# Schematic.net
KiCad netlist of a schematic drawn in EasyEDA
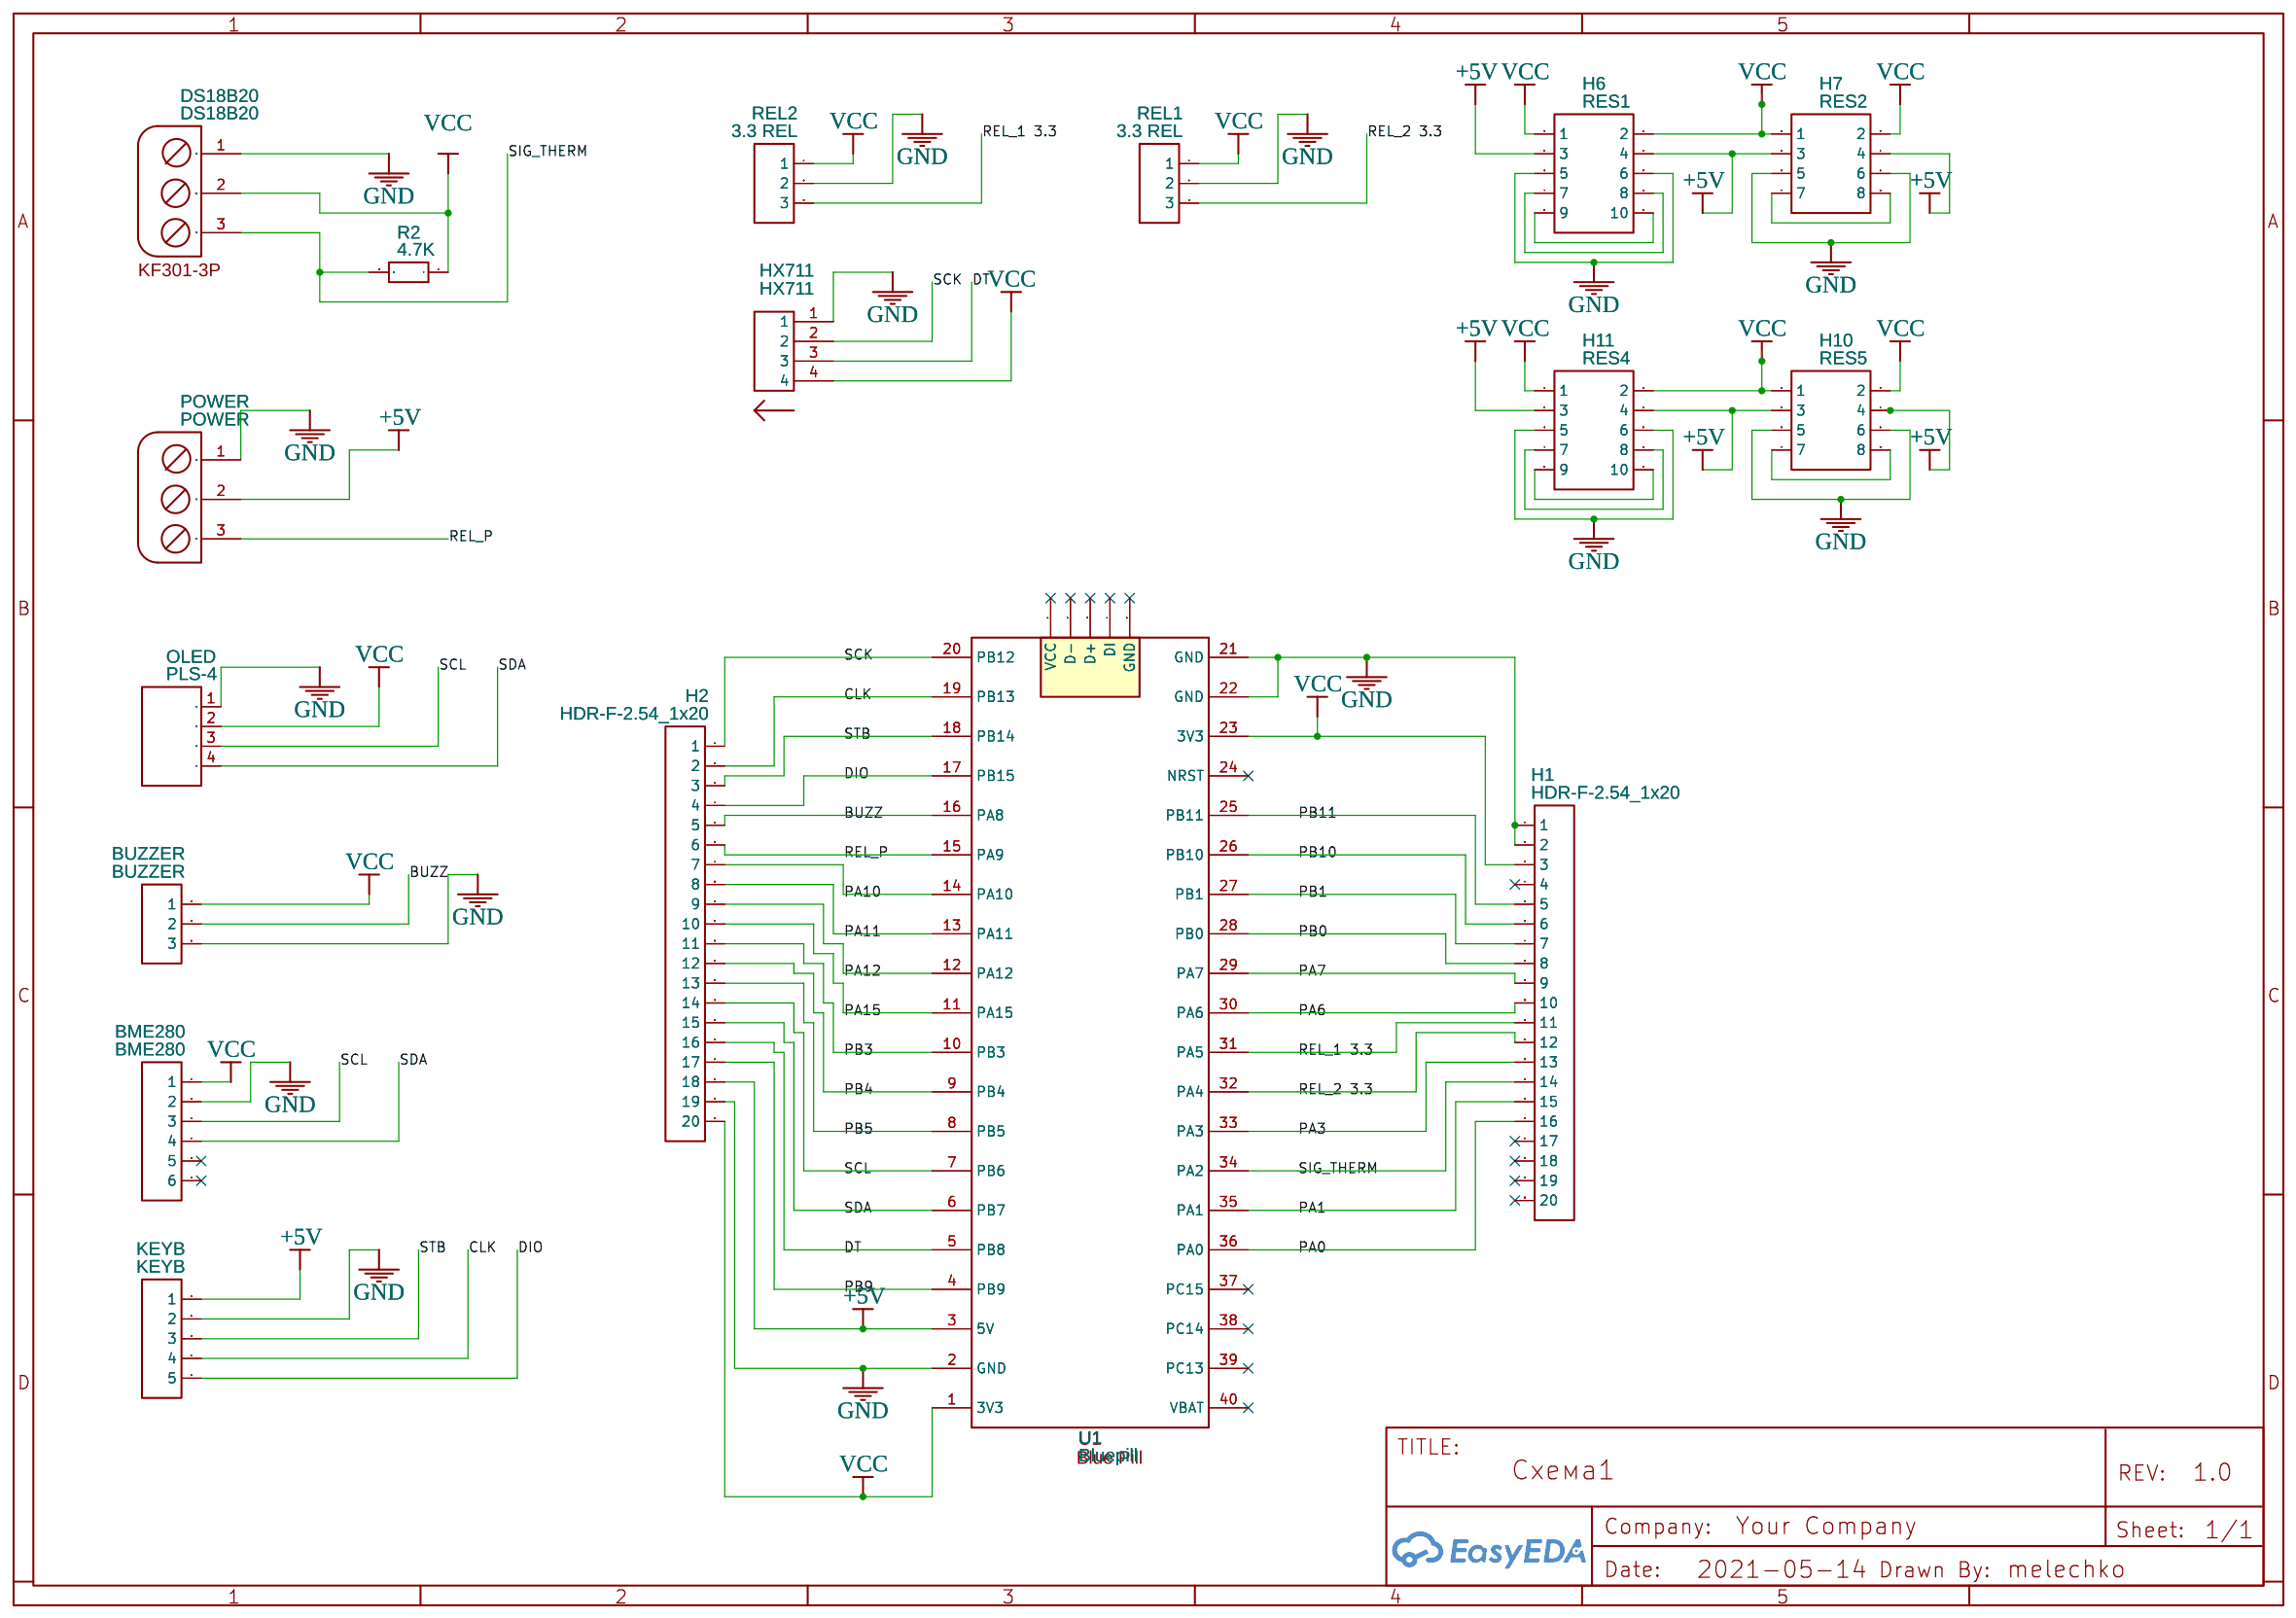
[diagram p0: schematic sheet]

(export (version "E")
  (design (tool "Eeschema 10.0.6"))
  (components
    (comp (ref "BME280")
      (value "BME280")
      (fields (field (name "BOM_Supplier Part") "C40877"))
      (libsource (lib "") (part "HDR-F-2.54_1x6"))
    )
    (comp (ref "BUZZER")
      (value "BUZZER")
      (fields (field (name "BOM_Supplier Part") "C146690"))
      (libsource (lib "") (part "HDR-F-2.54_1x3_1"))
    )
    (comp (ref "DS18B20") (value "DS18B20") (libsource (lib "") (part "KF301-3P")))
    (comp (ref "H1")
      (value "HDR-F-2.54_1x20")
      (fields (field (name "BOM_Supplier Part") "C50984"))
      (libsource (lib "") (part "HDR-F-2.54_1x20_1"))
    )
    (comp (ref "H2")
      (value "HDR-F-2.54_1x20")
      (fields (field (name "BOM_Supplier Part") "C50984"))
      (libsource (lib "") (part "HDR-F-2.54_1x20"))
    )
    (comp (ref "H6")
      (value "RES1")
      (fields (field (name "BOM_Supplier Part") "C30419"))
      (libsource (lib "") (part "HDR-F-2.54_2x5"))
    )
    (comp (ref "H7")
      (value "RES2")
      (fields (field (name "BOM_Supplier Part") "C239344"))
      (libsource (lib "") (part "HDR-F-2.54_2x4"))
    )
    (comp (ref "H10")
      (value "RES5")
      (fields (field (name "BOM_Supplier Part") "C239344"))
      (libsource (lib "") (part "HDR-F-2.54_2x4"))
    )
    (comp (ref "H11")
      (value "RES4")
      (fields (field (name "BOM_Supplier Part") "C30419"))
      (libsource (lib "") (part "HDR-F-2.54_2x5"))
    )
    (comp (ref "HX711")
      (value "HX711")
      (fields (field (name "BOM_Manufacturer Part") "PLS-4R (DS1022-1x4R)"))
      (libsource (lib "") (part "PLS-4R (DS1022-1x4R)"))
    )
    (comp (ref "KEYB")
      (value "KEYB")
      (fields (field (name "BOM_Supplier Part") "C50950"))
      (libsource (lib "") (part "HDR-F-2.54_1x5"))
    )
    (comp (ref "OLED")
      (value "PLS-4")
      (fields (field (name "BOM_Manufacturer Part") "PLS-4 2,54 1x4"))
      (libsource (lib "") (part "PLS-4"))
    )
    (comp (ref "POWER") (value "POWER") (libsource (lib "") (part "KF301-3P_1")))
    (comp (ref "R2")
      (value "4.7K")
      (fields
        (field (name "BOM_Manufacturer Part") "RN 1WS 4K7 F T/B A1")
        (field (name "BOM_Supplier Part") "C433646")
      )
      (libsource (lib "") (part "RN 1WS 4K7 F T/B A1"))
    )
    (comp (ref "REL1")
      (value "3.3 REL")
      (fields (field (name "BOM_Supplier Part") "C146690"))
      (libsource (lib "") (part "HDR-F-2.54_1x3"))
    )
    (comp (ref "REL2")
      (value "3.3 REL")
      (fields (field (name "BOM_Supplier Part") "C146690"))
      (libsource (lib "") (part "HDR-F-2.54_1x3"))
    )
    (comp (ref "U1") (value "Bluepill") (libsource (lib "") (part "Bluepill")))
  )
  (nets
    (net (code "1") (name "+5V") (class "Default")
      (node (ref "H10") (pin "3") (pinfunction "3_3") (pintype "unspecified"))
      (node (ref "H10") (pin "4") (pinfunction "4_4") (pintype "unspecified"))
      (node (ref "H11") (pin "3") (pinfunction "3_3") (pintype "unspecified"))
      (node (ref "H11") (pin "4") (pinfunction "4_4") (pintype "unspecified"))
      (node (ref "H2") (pin "18") (pinfunction "18_18") (pintype "unspecified"))
      (node (ref "H6") (pin "3") (pinfunction "3_3") (pintype "unspecified"))
      (node (ref "H6") (pin "4") (pinfunction "4_4") (pintype "unspecified"))
      (node (ref "H7") (pin "3") (pinfunction "3_3") (pintype "unspecified"))
      (node (ref "H7") (pin "4") (pinfunction "4_4") (pintype "unspecified"))
      (node (ref "KEYB") (pin "1") (pinfunction "1_1") (pintype "unspecified"))
      (node (ref "POWER") (pin "2") (pinfunction "2_2") (pintype "unspecified"))
      (node (ref "U1") (pin "3") (pinfunction "5V_3") (pintype "passive"))
    )
    (net (code "2") (name "/BUZZ") (class "Default")
      (node (ref "BUZZER") (pin "2") (pinfunction "2_2") (pintype "input"))
      (node (ref "H2") (pin "5") (pinfunction "5_5") (pintype "unspecified"))
      (node (ref "U1") (pin "16") (pinfunction "PA8_16") (pintype "bidirectional"))
    )
    (net (code "3") (name "/CLK") (class "Default")
      (node (ref "H2") (pin "2") (pinfunction "2_2") (pintype "unspecified"))
      (node (ref "KEYB") (pin "4") (pinfunction "4_4") (pintype "unspecified"))
      (node (ref "U1") (pin "19") (pinfunction "PB13_19") (pintype "bidirectional"))
    )
    (net (code "4") (name "/DIO") (class "Default")
      (node (ref "H2") (pin "4") (pinfunction "4_4") (pintype "unspecified"))
      (node (ref "KEYB") (pin "5") (pinfunction "5_5") (pintype "unspecified"))
      (node (ref "U1") (pin "17") (pinfunction "PB15_17") (pintype "bidirectional"))
    )
    (net (code "5") (name "/DT") (class "Default")
      (node (ref "H2") (pin "16") (pinfunction "16_16") (pintype "unspecified"))
      (node (ref "HX711") (pin "3") (pinfunction "3_3") (pintype "unspecified"))
      (node (ref "U1") (pin "5") (pinfunction "PB8_5") (pintype "bidirectional"))
    )
    (net (code "6") (name "/PA0") (class "Default")
      (node (ref "H1") (pin "16") (pinfunction "16_16") (pintype "unspecified"))
      (node (ref "U1") (pin "36") (pinfunction "PA0_36") (pintype "bidirectional"))
    )
    (net (code "7") (name "/PA1") (class "Default")
      (node (ref "H1") (pin "15") (pinfunction "15_15") (pintype "unspecified"))
      (node (ref "U1") (pin "35") (pinfunction "PA1_35") (pintype "bidirectional"))
    )
    (net (code "8") (name "/PA3") (class "Default")
      (node (ref "H1") (pin "13") (pinfunction "13_13") (pintype "unspecified"))
      (node (ref "U1") (pin "33") (pinfunction "PA3_33") (pintype "bidirectional"))
    )
    (net (code "9") (name "/PA6") (class "Default")
      (node (ref "H1") (pin "10") (pinfunction "10_10") (pintype "unspecified"))
      (node (ref "U1") (pin "30") (pinfunction "PA6_30") (pintype "bidirectional"))
    )
    (net (code "10") (name "/PA7") (class "Default")
      (node (ref "H1") (pin "9") (pinfunction "9_9") (pintype "unspecified"))
      (node (ref "U1") (pin "29") (pinfunction "PA7_29") (pintype "bidirectional"))
    )
    (net (code "11") (name "/PA10") (class "Default")
      (node (ref "H2") (pin "7") (pinfunction "7_7") (pintype "unspecified"))
      (node (ref "U1") (pin "14") (pinfunction "PA10_14") (pintype "bidirectional"))
    )
    (net (code "12") (name "/PA11") (class "Default")
      (node (ref "H2") (pin "8") (pinfunction "8_8") (pintype "unspecified"))
      (node (ref "U1") (pin "13") (pinfunction "PA11_13") (pintype "bidirectional"))
    )
    (net (code "13") (name "/PA12") (class "Default")
      (node (ref "H2") (pin "9") (pinfunction "9_9") (pintype "unspecified"))
      (node (ref "U1") (pin "12") (pinfunction "PA12_12") (pintype "bidirectional"))
    )
    (net (code "14") (name "/PA15") (class "Default")
      (node (ref "H2") (pin "10") (pinfunction "10_10") (pintype "unspecified"))
      (node (ref "U1") (pin "11") (pinfunction "PA15_11") (pintype "bidirectional"))
    )
    (net (code "15") (name "/PB0") (class "Default")
      (node (ref "H1") (pin "8") (pinfunction "8_8") (pintype "unspecified"))
      (node (ref "U1") (pin "28") (pinfunction "PB0_28") (pintype "bidirectional"))
    )
    (net (code "16") (name "/PB1") (class "Default")
      (node (ref "H1") (pin "7") (pinfunction "7_7") (pintype "unspecified"))
      (node (ref "U1") (pin "27") (pinfunction "PB1_27") (pintype "bidirectional"))
    )
    (net (code "17") (name "/PB3") (class "Default")
      (node (ref "H2") (pin "11") (pinfunction "11_11") (pintype "unspecified"))
      (node (ref "U1") (pin "10") (pinfunction "PB3_10") (pintype "unspecified"))
    )
    (net (code "18") (name "/PB4") (class "Default")
      (node (ref "H2") (pin "12") (pinfunction "12_12") (pintype "unspecified"))
      (node (ref "U1") (pin "9") (pinfunction "PB4_9") (pintype "bidirectional"))
    )
    (net (code "19") (name "/PB5") (class "Default")
      (node (ref "H2") (pin "13") (pinfunction "13_13") (pintype "unspecified"))
      (node (ref "U1") (pin "8") (pinfunction "PB5_8") (pintype "bidirectional"))
    )
    (net (code "20") (name "/PB9") (class "Default")
      (node (ref "H2") (pin "17") (pinfunction "17_17") (pintype "unspecified"))
      (node (ref "U1") (pin "4") (pinfunction "PB9_4") (pintype "bidirectional"))
    )
    (net (code "21") (name "/PB10") (class "Default")
      (node (ref "H1") (pin "6") (pinfunction "6_6") (pintype "unspecified"))
      (node (ref "U1") (pin "26") (pinfunction "PB10_26") (pintype "bidirectional"))
    )
    (net (code "22") (name "/PB11") (class "Default")
      (node (ref "H1") (pin "5") (pinfunction "5_5") (pintype "unspecified"))
      (node (ref "U1") (pin "25") (pinfunction "PB11_25") (pintype "bidirectional"))
    )
    (net (code "23") (name "/REL_1 3.3") (class "Default")
      (node (ref "H1") (pin "11") (pinfunction "11_11") (pintype "unspecified"))
      (node (ref "REL2") (pin "3") (pinfunction "3_3") (pintype "input"))
      (node (ref "U1") (pin "31") (pinfunction "PA5_31") (pintype "bidirectional"))
    )
    (net (code "24") (name "/REL_2 3.3") (class "Default")
      (node (ref "H1") (pin "12") (pinfunction "12_12") (pintype "unspecified"))
      (node (ref "REL1") (pin "3") (pinfunction "3_3") (pintype "input"))
      (node (ref "U1") (pin "32") (pinfunction "PA4_32") (pintype "bidirectional"))
    )
    (net (code "25") (name "/REL_P") (class "Default")
      (node (ref "H2") (pin "6") (pinfunction "6_6") (pintype "unspecified"))
      (node (ref "POWER") (pin "3") (pinfunction "3_3") (pintype "unspecified"))
      (node (ref "U1") (pin "15") (pinfunction "PA9_15") (pintype "bidirectional"))
    )
    (net (code "26") (name "/SCK") (class "Default")
      (node (ref "H2") (pin "1") (pinfunction "1_1") (pintype "unspecified"))
      (node (ref "HX711") (pin "2") (pinfunction "2_2") (pintype "unspecified"))
      (node (ref "U1") (pin "20") (pinfunction "PB12_20") (pintype "bidirectional"))
    )
    (net (code "27") (name "/SCL") (class "Default")
      (node (ref "BME280") (pin "3") (pinfunction "3_3") (pintype "input"))
      (node (ref "H2") (pin "14") (pinfunction "14_14") (pintype "unspecified"))
      (node (ref "OLED") (pin "3") (pinfunction "3_3") (pintype "unspecified"))
      (node (ref "U1") (pin "7") (pinfunction "PB6_7") (pintype "bidirectional"))
    )
    (net (code "28") (name "/SDA") (class "Default")
      (node (ref "BME280") (pin "4") (pinfunction "4_4") (pintype "input"))
      (node (ref "H2") (pin "15") (pinfunction "15_15") (pintype "unspecified"))
      (node (ref "OLED") (pin "4") (pinfunction "4_4") (pintype "unspecified"))
      (node (ref "U1") (pin "6") (pinfunction "PB7_6") (pintype "bidirectional"))
    )
    (net (code "29") (name "/SIG_THERM") (class "Default")
      (node (ref "DS18B20") (pin "3") (pinfunction "SIG_3") (pintype "unspecified"))
      (node (ref "H1") (pin "14") (pinfunction "14_14") (pintype "unspecified"))
      (node (ref "R2") (pin "2") (pinfunction "2_2") (pintype "unspecified"))
      (node (ref "U1") (pin "34") (pinfunction "PA2_34") (pintype "bidirectional"))
    )
    (net (code "30") (name "/STB") (class "Default")
      (node (ref "H2") (pin "3") (pinfunction "3_3") (pintype "unspecified"))
      (node (ref "KEYB") (pin "3") (pinfunction "3_3") (pintype "unspecified"))
      (node (ref "U1") (pin "18") (pinfunction "PB14_18") (pintype "bidirectional"))
    )
    (net (code "31") (name "GND") (class "Default")
      (node (ref "BME280") (pin "2") (pinfunction "2_2") (pintype "input"))
      (node (ref "BUZZER") (pin "3") (pinfunction "3_3") (pintype "input"))
      (node (ref "DS18B20") (pin "1") (pinfunction "VCC_1") (pintype "unspecified"))
      (node (ref "H1") (pin "1") (pinfunction "1_1") (pintype "unspecified"))
      (node (ref "H1") (pin "2") (pinfunction "2_2") (pintype "unspecified"))
      (node (ref "H10") (pin "5") (pinfunction "5_5") (pintype "unspecified"))
      (node (ref "H10") (pin "6") (pinfunction "6_6") (pintype "unspecified"))
      (node (ref "H11") (pin "5") (pinfunction "5_5") (pintype "unspecified"))
      (node (ref "H11") (pin "6") (pinfunction "6_6") (pintype "unspecified"))
      (node (ref "H2") (pin "19") (pinfunction "19_19") (pintype "unspecified"))
      (node (ref "H6") (pin "5") (pinfunction "5_5") (pintype "unspecified"))
      (node (ref "H6") (pin "6") (pinfunction "6_6") (pintype "unspecified"))
      (node (ref "H7") (pin "5") (pinfunction "5_5") (pintype "unspecified"))
      (node (ref "H7") (pin "6") (pinfunction "6_6") (pintype "unspecified"))
      (node (ref "HX711") (pin "1") (pinfunction "1_1") (pintype "unspecified"))
      (node (ref "KEYB") (pin "2") (pinfunction "2_2") (pintype "unspecified"))
      (node (ref "OLED") (pin "1") (pinfunction "1_1") (pintype "unspecified"))
      (node (ref "POWER") (pin "1") (pinfunction "1_1") (pintype "unspecified"))
      (node (ref "REL1") (pin "2") (pinfunction "2_2") (pintype "input"))
      (node (ref "REL2") (pin "2") (pinfunction "2_2") (pintype "input"))
      (node (ref "U1") (pin "2") (pinfunction "GND_2") (pintype "passive"))
      (node (ref "U1") (pin "21") (pinfunction "GND_21") (pintype "passive"))
      (node (ref "U1") (pin "22") (pinfunction "GND_22") (pintype "passive"))
    )
    (net (code "32") (name "Net-(H6-Pad7)") (class "Default")
      (node (ref "H6") (pin "7") (pinfunction "7_7") (pintype "unspecified"))
      (node (ref "H6") (pin "8") (pinfunction "8_8") (pintype "unspecified"))
    )
    (net (code "33") (name "Net-(H6-Pad10)") (class "Default")
      (node (ref "H6") (pin "10") (pinfunction "10_10") (pintype "unspecified"))
      (node (ref "H6") (pin "9") (pinfunction "9_9") (pintype "unspecified"))
    )
    (net (code "34") (name "Net-(H7-Pad7)") (class "Default")
      (node (ref "H7") (pin "7") (pinfunction "7_7") (pintype "unspecified"))
      (node (ref "H7") (pin "8") (pinfunction "8_8") (pintype "unspecified"))
    )
    (net (code "35") (name "Net-(H10-Pad7)") (class "Default")
      (node (ref "H10") (pin "7") (pinfunction "7_7") (pintype "unspecified"))
      (node (ref "H10") (pin "8") (pinfunction "8_8") (pintype "unspecified"))
    )
    (net (code "36") (name "Net-(H11-Pad7)") (class "Default")
      (node (ref "H11") (pin "7") (pinfunction "7_7") (pintype "unspecified"))
      (node (ref "H11") (pin "8") (pinfunction "8_8") (pintype "unspecified"))
    )
    (net (code "37") (name "Net-(H11-Pad10)") (class "Default")
      (node (ref "H11") (pin "10") (pinfunction "10_10") (pintype "unspecified"))
      (node (ref "H11") (pin "9") (pinfunction "9_9") (pintype "unspecified"))
    )
    (net (code "38") (name "VCC") (class "Default")
      (node (ref "BME280") (pin "1") (pinfunction "1_1") (pintype "input"))
      (node (ref "BUZZER") (pin "1") (pinfunction "1_1") (pintype "input"))
      (node (ref "DS18B20") (pin "2") (pinfunction "GND_2") (pintype "unspecified"))
      (node (ref "H1") (pin "3") (pinfunction "3_3") (pintype "unspecified"))
      (node (ref "H10") (pin "1") (pinfunction "1_1") (pintype "unspecified"))
      (node (ref "H10") (pin "2") (pinfunction "2_2") (pintype "unspecified"))
      (node (ref "H11") (pin "1") (pinfunction "1_1") (pintype "unspecified"))
      (node (ref "H11") (pin "2") (pinfunction "2_2") (pintype "unspecified"))
      (node (ref "H2") (pin "20") (pinfunction "20_20") (pintype "unspecified"))
      (node (ref "H6") (pin "1") (pinfunction "1_1") (pintype "unspecified"))
      (node (ref "H6") (pin "2") (pinfunction "2_2") (pintype "unspecified"))
      (node (ref "H7") (pin "1") (pinfunction "1_1") (pintype "unspecified"))
      (node (ref "H7") (pin "2") (pinfunction "2_2") (pintype "unspecified"))
      (node (ref "HX711") (pin "4") (pinfunction "4_4") (pintype "unspecified"))
      (node (ref "OLED") (pin "2") (pinfunction "2_2") (pintype "unspecified"))
      (node (ref "R2") (pin "1") (pinfunction "1_1") (pintype "unspecified"))
      (node (ref "REL1") (pin "1") (pinfunction "1_1") (pintype "input"))
      (node (ref "REL2") (pin "1") (pinfunction "1_1") (pintype "input"))
      (node (ref "U1") (pin "1") (pinfunction "3V3_1") (pintype "passive"))
      (node (ref "U1") (pin "23") (pinfunction "3V3_23") (pintype "passive"))
    )
    (net (code "39") (name "unconnected-(BME280-Pad5)") (class "Default")
      (node (ref "BME280") (pin "5") (pinfunction "5_5") (pintype "input+no_connect"))
    )
    (net (code "40") (name "unconnected-(BME280-Pad6)") (class "Default")
      (node (ref "BME280") (pin "6") (pinfunction "6_6") (pintype "input+no_connect"))
    )
    (net (code "41") (name "unconnected-(H1-Pad4)") (class "Default")
      (node (ref "H1") (pin "4") (pinfunction "4_4") (pintype "unspecified+no_connect"))
    )
    (net (code "42") (name "unconnected-(H1-Pad17)") (class "Default")
      (node (ref "H1") (pin "17") (pinfunction "17_17") (pintype "unspecified+no_connect"))
    )
    (net (code "43") (name "unconnected-(H1-Pad18)") (class "Default")
      (node (ref "H1") (pin "18") (pinfunction "18_18") (pintype "unspecified+no_connect"))
    )
    (net (code "44") (name "unconnected-(H1-Pad19)") (class "Default")
      (node (ref "H1") (pin "19") (pinfunction "19_19") (pintype "unspecified+no_connect"))
    )
    (net (code "45") (name "unconnected-(H1-Pad20)") (class "Default")
      (node (ref "H1") (pin "20") (pinfunction "20_20") (pintype "unspecified+no_connect"))
    )
    (net (code "46") (name "unconnected-(U1-D+-Pad3)") (class "Default")
      (node (ref "U1") (pin "3") (pinfunction "D+_3") (pintype "input+no_connect"))
    )
    (net (code "47") (name "unconnected-(U1-D--Pad2)") (class "Default")
      (node (ref "U1") (pin "2") (pinfunction "D-_2") (pintype "input+no_connect"))
    )
    (net (code "48") (name "unconnected-(U1-DI-Pad4)") (class "Default")
      (node (ref "U1") (pin "4") (pinfunction "DI_4") (pintype "input+no_connect"))
    )
    (net (code "49") (name "unconnected-(U1-GND-Pad5)") (class "Default")
      (node (ref "U1") (pin "5") (pinfunction "GND_5") (pintype "input+no_connect"))
    )
    (net (code "50") (name "unconnected-(U1-NRST-Pad24)") (class "Default")
      (node (ref "U1") (pin "24") (pinfunction "NRST_24") (pintype "input+no_connect"))
    )
    (net (code "51") (name "unconnected-(U1-PC13-Pad39)") (class "Default")
      (node (ref "U1") (pin "39") (pinfunction "PC13_39") (pintype "bidirectional+no_connect"))
    )
    (net (code "52") (name "unconnected-(U1-PC14-Pad38)") (class "Default")
      (node (ref "U1") (pin "38") (pinfunction "PC14_38") (pintype "bidirectional+no_connect"))
    )
    (net (code "53") (name "unconnected-(U1-PC15-Pad37)") (class "Default")
      (node (ref "U1") (pin "37") (pinfunction "PC15_37") (pintype "bidirectional+no_connect"))
    )
    (net (code "54") (name "unconnected-(U1-VBAT-Pad40)") (class "Default")
      (node (ref "U1") (pin "40") (pinfunction "VBAT_40") (pintype "passive+no_connect"))
    )
    (net (code "55") (name "unconnected-(U1-VCC-Pad1)") (class "Default")
      (node (ref "U1") (pin "1") (pinfunction "VCC_1") (pintype "input+no_connect"))
    )
  )
)
